# ranback_all.net
KiCad netlist of a schematic drawn in EAGLE
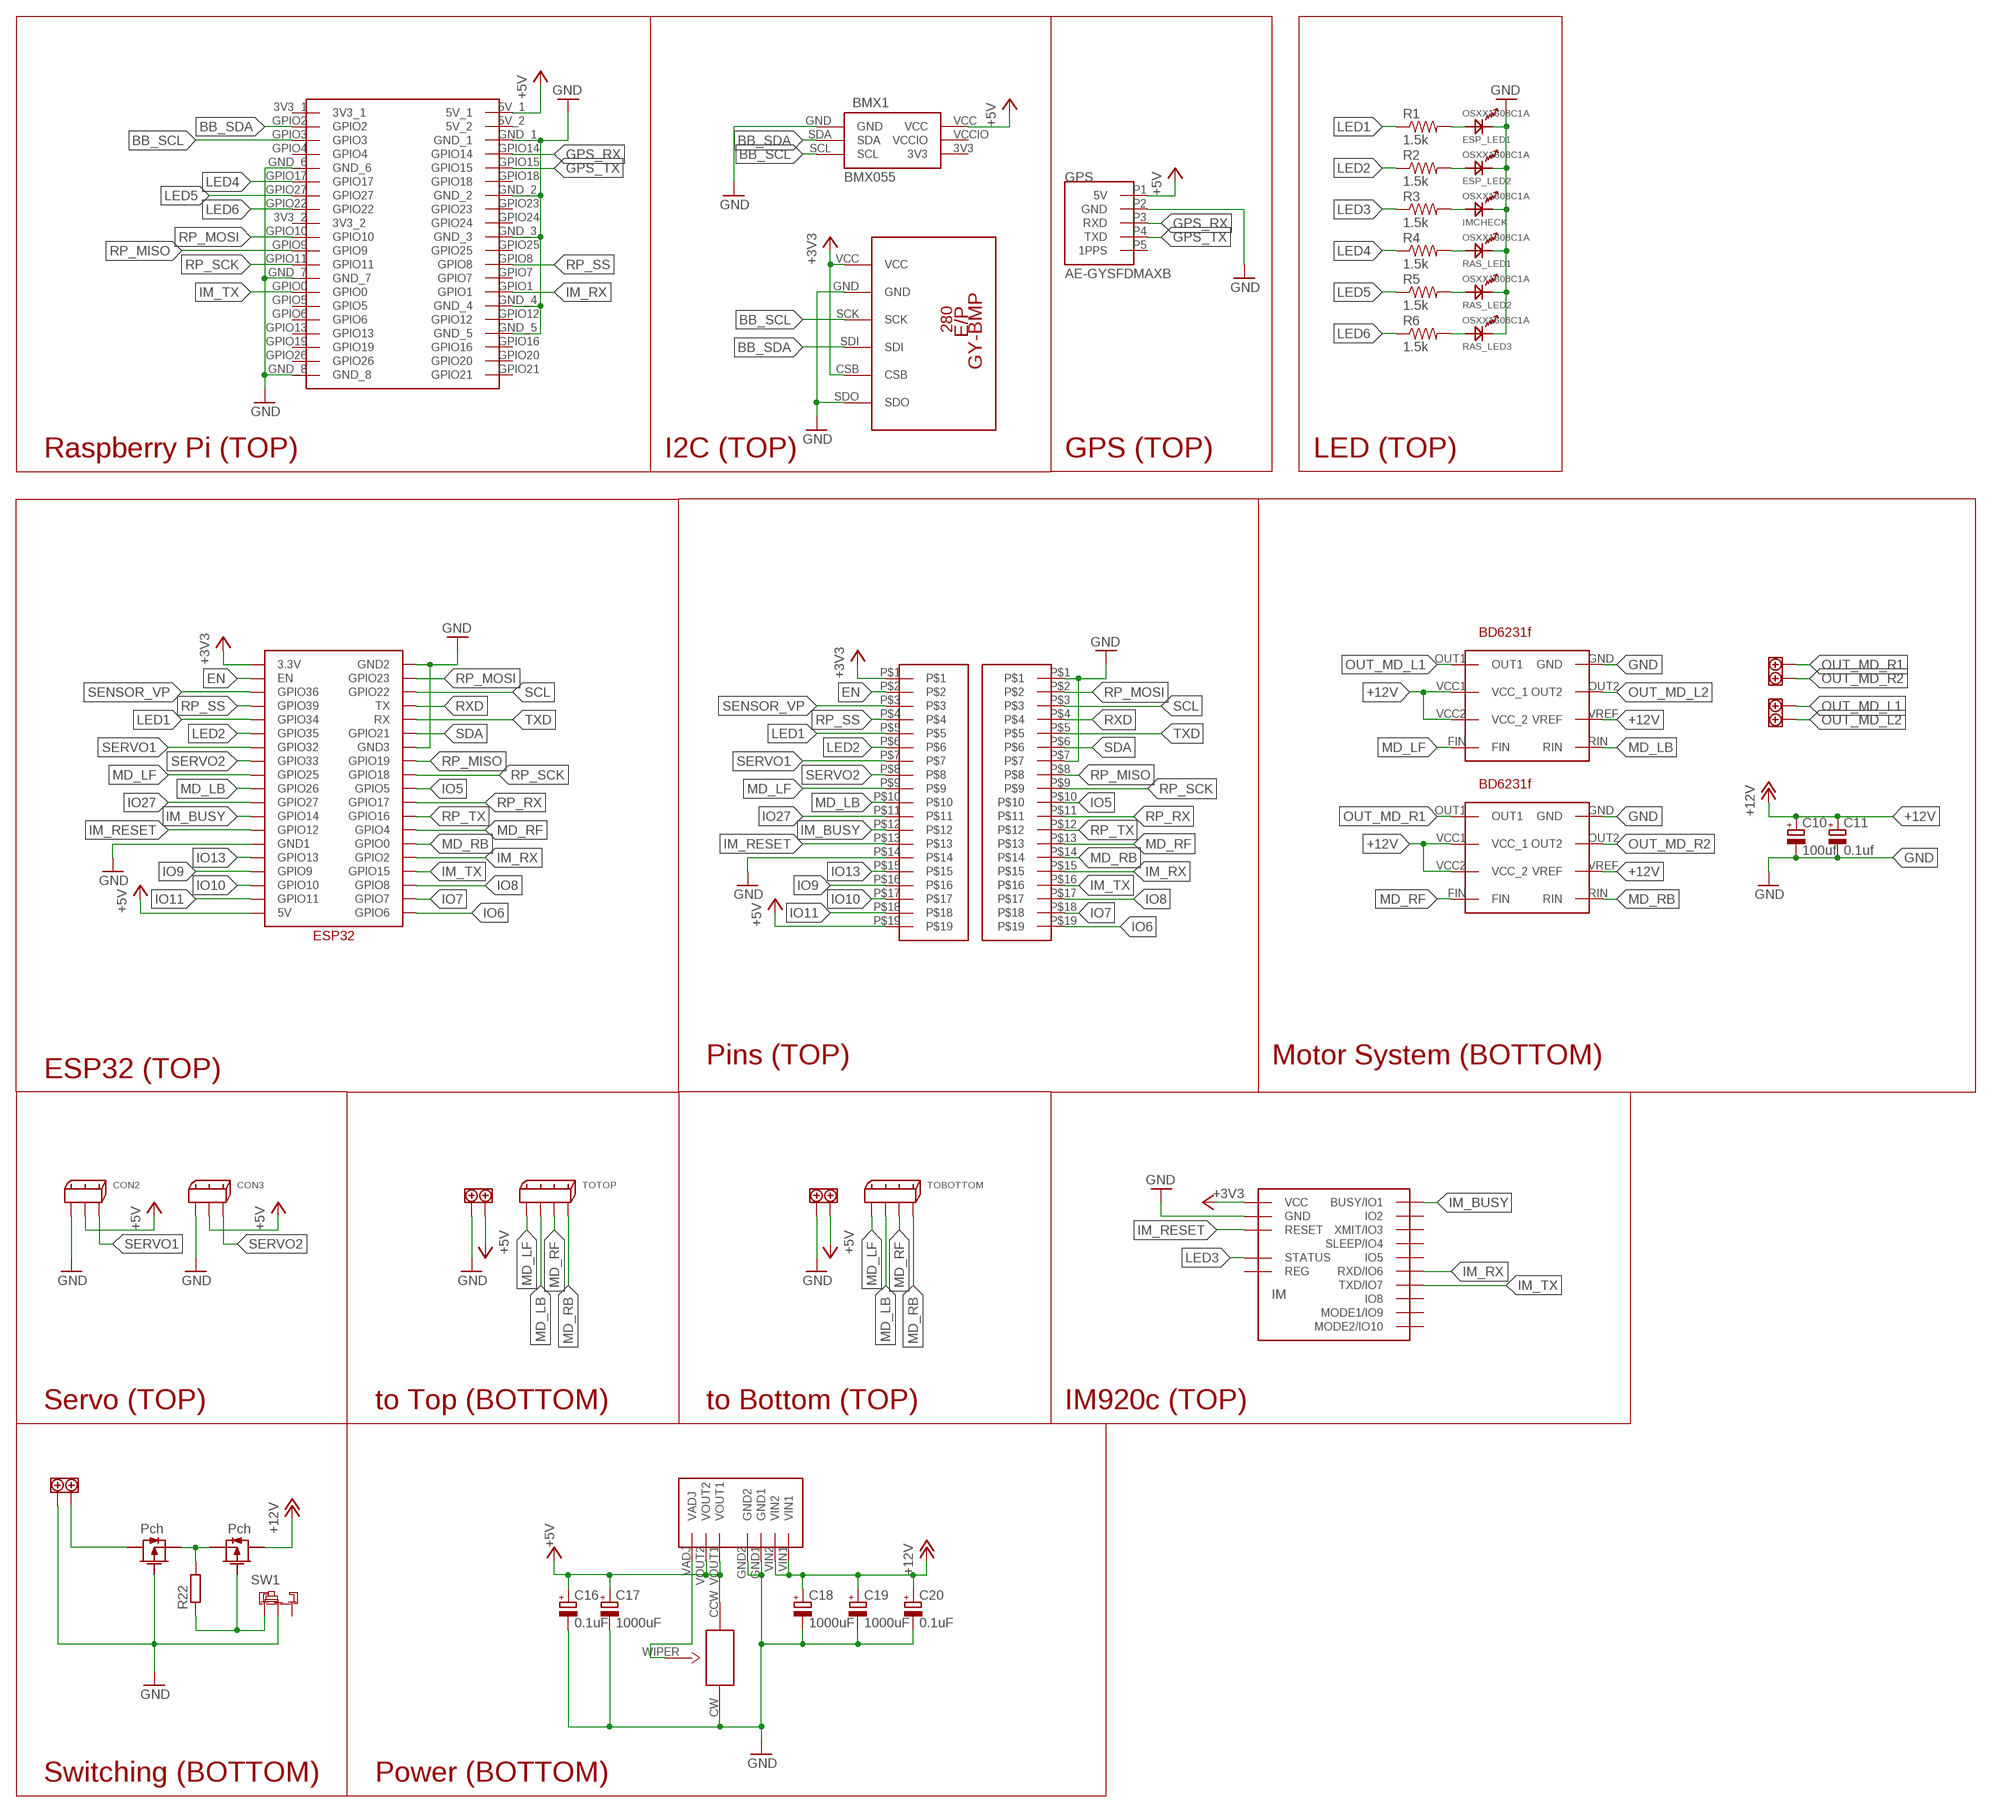
[diagram p0: schematic, sheet 1]

(export (version "E")
  (design (tool "Eeschema 10.0.6"))
  (components
    (comp (ref "100KR1")
      (value "100kR")
      (footprint "eagle-import:3362P")
      (libsource (lib "eagle-import") (part "3362P"))
    )
    (comp (ref "BMX1")
      (value "BMX055")
      (footprint "eagle-import:BMX055")
      (libsource (lib "eagle-import") (part "BMX055"))
    )
    (comp (ref "C10")
      (value "100uf")
      (footprint "eagle-import:E2,5-7")
      (libsource (lib "eagle-import") (part "CPOL-EUE2.5-7"))
    )
    (comp (ref "C11")
      (value "0.1uf")
      (footprint "eagle-import:E2,5-7")
      (libsource (lib "eagle-import") (part "CPOL-EUE2.5-7"))
    )
    (comp (ref "C16")
      (value "0.1uF")
      (footprint "eagle-import:E2,5-7")
      (libsource (lib "eagle-import") (part "CPOL-EUE2.5-7"))
    )
    (comp (ref "C17")
      (value "1000uF")
      (footprint "eagle-import:E5-10,5")
      (libsource (lib "eagle-import") (part "CPOL-EUE5-10.5"))
    )
    (comp (ref "C18")
      (value "1000uF")
      (footprint "eagle-import:E5-10,5")
      (libsource (lib "eagle-import") (part "CPOL-EUE5-10.5"))
    )
    (comp (ref "C19")
      (value "1000uF")
      (footprint "eagle-import:E5-10,5")
      (libsource (lib "eagle-import") (part "CPOL-EUE5-10.5"))
    )
    (comp (ref "C20")
      (value "0.1uF")
      (footprint "eagle-import:E2,5-7")
      (libsource (lib "eagle-import") (part "CPOL-EUE2.5-7"))
    )
    (comp (ref "CON2")
      (value "2.5_MINI-SPOX_3PIN")
      (footprint "eagle-import:2.5_MINI-SPOX_3PIN")
      (libsource (lib "eagle-import") (part "2.5_MINI-SPOX_3PIN"))
    )
    (comp (ref "CON3")
      (value "2.5_MINI-SPOX_3PIN")
      (footprint "eagle-import:2.5_MINI-SPOX_3PIN")
      (libsource (lib "eagle-import") (part "2.5_MINI-SPOX_3PIN"))
    )
    (comp (ref "ESP_LED1")
      (value "OSXX1608C1A")
      (footprint "eagle-import:OSXX1608C1A")
      (libsource (lib "eagle-import") (part "OSXX1608C1A"))
    )
    (comp (ref "ESP_LED2")
      (value "OSXX1608C1A")
      (footprint "eagle-import:OSXX1608C1A")
      (libsource (lib "eagle-import") (part "OSXX1608C1A"))
    )
    (comp (ref "GPS")
      (value "AE-GYSFDMAXB")
      (footprint "eagle-import:AE-GYSFDMAXB")
      (libsource (lib "eagle-import") (part "AE-GYSFDMAXB"))
    )
    (comp (ref "IM")
      (value "IM920C")
      (footprint "eagle-import:IM920C")
      (libsource (lib "eagle-import") (part "IM920C"))
    )
    (comp (ref "IMCHECK")
      (value "OSXX1608C1A")
      (footprint "eagle-import:OSXX1608C1A")
      (libsource (lib "eagle-import") (part "OSXX1608C1A"))
    )
    (comp (ref "MD_L")
      (value "BD6231F")
      (footprint "eagle-import:BD6231F")
      (libsource (lib "eagle-import") (part "BD6231F"))
    )
    (comp (ref "MD_R")
      (value "BD6231F")
      (footprint "eagle-import:BD6231F")
      (libsource (lib "eagle-import") (part "BD6231F"))
    )
    (comp (ref "PIN_L")
      (value "19_2.54")
      (footprint "eagle-import:19_2.54")
      (libsource (lib "eagle-import") (part "19_2.54"))
    )
    (comp (ref "PIN_R")
      (value "19_2.54")
      (footprint "eagle-import:19_2.54")
      (libsource (lib "eagle-import") (part "19_2.54"))
    )
    (comp (ref "R1")
      (value "1.5k")
      (footprint "eagle-import:R0603")
      (libsource (lib "eagle-import") (part "R-US_R0603"))
    )
    (comp (ref "R2")
      (value "1.5k")
      (footprint "eagle-import:R0603")
      (libsource (lib "eagle-import") (part "R-US_R0603"))
    )
    (comp (ref "R3")
      (value "1.5k")
      (footprint "eagle-import:R0603")
      (libsource (lib "eagle-import") (part "R-US_R0603"))
    )
    (comp (ref "R4")
      (value "1.5k")
      (footprint "eagle-import:R0603")
      (libsource (lib "eagle-import") (part "R-US_R0603"))
    )
    (comp (ref "R5")
      (value "1.5k")
      (footprint "eagle-import:R0603")
      (libsource (lib "eagle-import") (part "R-US_R0603"))
    )
    (comp (ref "R6")
      (value "1.5k")
      (footprint "eagle-import:R0603")
      (libsource (lib "eagle-import") (part "R-US_R0603"))
    )
    (comp (ref "R22")
      (value "R-EU_0207/10")
      (footprint "eagle-import:0207_10")
      (libsource (lib "eagle-import") (part "R-EU_0207/10"))
    )
    (comp (ref "RASPBERRYPI_4B")
      (value "RASPBERRYPI4B")
      (footprint "eagle-import:RASPBERRYPI4B")
      (libsource (lib "eagle-import") (part "RASPBERRYPI4B"))
    )
    (comp (ref "RAS_LED1")
      (value "OSXX1608C1A")
      (footprint "eagle-import:OSXX1608C1A")
      (libsource (lib "eagle-import") (part "OSXX1608C1A"))
    )
    (comp (ref "RAS_LED2")
      (value "OSXX1608C1A")
      (footprint "eagle-import:OSXX1608C1A")
      (libsource (lib "eagle-import") (part "OSXX1608C1A"))
    )
    (comp (ref "RAS_LED3")
      (value "OSXX1608C1A")
      (footprint "eagle-import:OSXX1608C1A")
      (libsource (lib "eagle-import") (part "OSXX1608C1A"))
    )
    (comp (ref "SW1")
      (value "SRIDE_SWITCH")
      (footprint "eagle-import:SRIDE_SWITCH")
      (libsource (lib "eagle-import") (part "SRIDE_SWITCH"))
    )
    (comp (ref "TM1")
      (value "TERMINAL_SLOPED_2PIN")
      (footprint "eagle-import:TERMINAL_SLOPED_2PIN")
      (libsource (lib "eagle-import") (part "TERMINAL_SLOPED_2PIN"))
    )
    (comp (ref "TM2")
      (value "TERMINAL_SLOPED_2PIN")
      (footprint "eagle-import:TERMINAL_SLOPED_2PIN")
      (libsource (lib "eagle-import") (part "TERMINAL_SLOPED_2PIN"))
    )
    (comp (ref "TM3")
      (value "TERMINAL_SLOPED_2PIN")
      (footprint "eagle-import:TERMINAL_SLOPED_2PIN")
      (libsource (lib "eagle-import") (part "TERMINAL_SLOPED_2PIN"))
    )
    (comp (ref "TM4")
      (value "TERMINAL_SLOPED_2PIN")
      (footprint "eagle-import:TERMINAL_SLOPED_2PIN")
      (libsource (lib "eagle-import") (part "TERMINAL_SLOPED_2PIN"))
    )
    (comp (ref "TM5")
      (value "TERMINAL_SLOPED_2PIN")
      (footprint "eagle-import:TERMINAL_SLOPED_2PIN")
      (libsource (lib "eagle-import") (part "TERMINAL_SLOPED_2PIN"))
    )
    (comp (ref "TOBOTTOM")
      (value "2.5_MINI-SPOX_4PIN")
      (footprint "eagle-import:2.5_MINI-SPOX_4PIN")
      (libsource (lib "eagle-import") (part "2.5_MINI-SPOX_4PIN"))
    )
    (comp (ref "TOTOP")
      (value "2.5_MINI-SPOX_4PIN")
      (footprint "eagle-import:2.5_MINI-SPOX_4PIN")
      (libsource (lib "eagle-import") (part "2.5_MINI-SPOX_4PIN"))
    )
    (comp (ref "U$2")
      (value "ESP32")
      (footprint "eagle-import:ESP32")
      (libsource (lib "eagle-import") (part "ESP32"))
    )
    (comp (ref "U$7")
      (value "2SJ681-PCH")
      (footprint "eagle-import:2SJ681")
      (libsource (lib "eagle-import") (part "2SJ681-PCH"))
    )
    (comp (ref "U$8")
      (value "5V3A_KIC-053")
      (footprint "eagle-import:5V3A_KIC-053")
      (libsource (lib "eagle-import") (part "5V3A_KIC-053"))
    )
    (comp (ref "U$9")
      (value "GY-BPM280")
      (footprint "eagle-import:GY-BMP280-FOOTPRINT")
      (libsource (lib "eagle-import") (part "GY-BPM280"))
    )
    (comp (ref "U$10")
      (value "2SJ681-PCH")
      (footprint "eagle-import:2SJ681")
      (libsource (lib "eagle-import") (part "2SJ681-PCH"))
    )
  )
  (nets
    (net (code "1") (name "+3V3") (class "Default")
      (node (ref "IM") (pin "$P17") (pinfunction "VCC_$P17") (pintype "bidirectional"))
      (node (ref "PIN_L") (pin "P$1") (pinfunction "P$1_P$1") (pintype "bidirectional"))
      (node (ref "U$2") (pin "3.3V") (pinfunction "3.3V_3.3V") (pintype "bidirectional"))
      (node (ref "U$9") (pin "CSB") (pinfunction "CSB_CSB") (pintype "bidirectional"))
      (node (ref "U$9") (pin "VCC") (pinfunction "VCC_VCC") (pintype "bidirectional"))
    )
    (net (code "2") (name "+5V") (class "Default")
      (node (ref "100KR1") (pin "CCW") (pinfunction "CCW_CCW") (pintype "bidirectional"))
      (node (ref "BMX1") (pin "VCC") (pinfunction "VCC_VCC") (pintype "power_in"))
      (node (ref "C16") (pin "+") (pinfunction "+_+") (pintype "passive"))
      (node (ref "C17") (pin "+") (pinfunction "+_+") (pintype "passive"))
      (node (ref "CON2") (pin "2") (pinfunction "2_2") (pintype "bidirectional"))
      (node (ref "CON3") (pin "2") (pinfunction "2_2") (pintype "bidirectional"))
      (node (ref "GPS") (pin "P1") (pinfunction "5V_P1") (pintype "bidirectional"))
      (node (ref "PIN_L") (pin "P$19") (pinfunction "P$19_P$19") (pintype "bidirectional"))
      (node (ref "RASPBERRYPI_4B") (pin "5V_1") (pinfunction "5V_1_5V_1") (pintype "bidirectional"))
      (node (ref "TM4") (pin "1") (pinfunction "1_1") (pintype "bidirectional"))
      (node (ref "TM5") (pin "1") (pinfunction "1_1") (pintype "bidirectional"))
      (node (ref "U$2") (pin "5V") (pinfunction "5V_5V") (pintype "bidirectional"))
      (node (ref "U$8") (pin "VOUT1") (pinfunction "VOUT1_VOUT1") (pintype "bidirectional"))
      (node (ref "U$8") (pin "VOUT2") (pinfunction "VOUT2_VOUT2") (pintype "bidirectional"))
    )
    (net (code "3") (name "+12V") (class "Default")
      (node (ref "C10") (pin "+") (pinfunction "+_+") (pintype "passive"))
      (node (ref "C11") (pin "+") (pinfunction "+_+") (pintype "passive"))
      (node (ref "C18") (pin "+") (pinfunction "+_+") (pintype "passive"))
      (node (ref "C19") (pin "+") (pinfunction "+_+") (pintype "passive"))
      (node (ref "C20") (pin "+") (pinfunction "+_+") (pintype "passive"))
      (node (ref "MD_L") (pin "VCC1") (pinfunction "VCC_1_VCC1") (pintype "bidirectional"))
      (node (ref "MD_L") (pin "VCC2") (pinfunction "VCC_2_VCC2") (pintype "bidirectional"))
      (node (ref "MD_L") (pin "VREF") (pinfunction "VREF_VREF") (pintype "bidirectional"))
      (node (ref "MD_R") (pin "VCC1") (pinfunction "VCC_1_VCC1") (pintype "bidirectional"))
      (node (ref "MD_R") (pin "VCC2") (pinfunction "VCC_2_VCC2") (pintype "bidirectional"))
      (node (ref "MD_R") (pin "VREF") (pinfunction "VREF_VREF") (pintype "bidirectional"))
      (node (ref "U$10") (pin "DRAIN") (pinfunction "DRAIN_DRAIN") (pintype "bidirectional"))
      (node (ref "U$8") (pin "VIN1") (pinfunction "VIN1_VIN1") (pintype "bidirectional"))
      (node (ref "U$8") (pin "VIN2") (pinfunction "VIN2_VIN2") (pintype "bidirectional"))
    )
    (net (code "4") (name "/3V3") (class "Default")
      (node (ref "BMX1") (pin "3V3") (pinfunction "3V3_3V3") (pintype "power_in"))
    )
    (net (code "5") (name "/VCCIO") (class "Default")
      (node (ref "BMX1") (pin "VCCIO") (pinfunction "VCCIO_VCCIO") (pintype "power_in"))
    )
    (net (code "6") (name "BB_SCL") (class "Default")
      (node (ref "BMX1") (pin "SCL") (pinfunction "SCL_SCL") (pintype "bidirectional"))
      (node (ref "RASPBERRYPI_4B") (pin "GPIO3") (pinfunction "GPIO3_GPIO3") (pintype "bidirectional"))
      (node (ref "U$9") (pin "SCK") (pinfunction "SCK_SCK") (pintype "bidirectional"))
    )
    (net (code "7") (name "BB_SDA") (class "Default")
      (node (ref "BMX1") (pin "SDA") (pinfunction "SDA_SDA") (pintype "bidirectional"))
      (node (ref "RASPBERRYPI_4B") (pin "GPIO2") (pinfunction "GPIO2_GPIO2") (pintype "bidirectional"))
      (node (ref "U$9") (pin "SDI") (pinfunction "SDI_SDI") (pintype "bidirectional"))
    )
    (net (code "8") (name "EN") (class "Default")
      (node (ref "PIN_L") (pin "P$2") (pinfunction "P$2_P$2") (pintype "bidirectional"))
      (node (ref "U$2") (pin "EN") (pinfunction "EN_EN") (pintype "bidirectional"))
    )
    (net (code "9") (name "GND") (class "Default")
      (node (ref "100KR1") (pin "CW") (pinfunction "CW_CW") (pintype "bidirectional"))
      (node (ref "BMX1") (pin "GND") (pinfunction "GND_GND") (pintype "power_in"))
      (node (ref "C10") (pin "-") (pinfunction "-_-") (pintype "passive"))
      (node (ref "C11") (pin "-") (pinfunction "-_-") (pintype "passive"))
      (node (ref "C16") (pin "-") (pinfunction "-_-") (pintype "passive"))
      (node (ref "C17") (pin "-") (pinfunction "-_-") (pintype "passive"))
      (node (ref "C18") (pin "-") (pinfunction "-_-") (pintype "passive"))
      (node (ref "C19") (pin "-") (pinfunction "-_-") (pintype "passive"))
      (node (ref "C20") (pin "-") (pinfunction "-_-") (pintype "passive"))
      (node (ref "CON2") (pin "1") (pinfunction "1_1") (pintype "bidirectional"))
      (node (ref "CON3") (pin "1") (pinfunction "1_1") (pintype "bidirectional"))
      (node (ref "ESP_LED1") (pin "CT") (pinfunction "CT_CT") (pintype "bidirectional"))
      (node (ref "ESP_LED2") (pin "CT") (pinfunction "CT_CT") (pintype "bidirectional"))
      (node (ref "GPS") (pin "P2") (pinfunction "GND_P2") (pintype "bidirectional"))
      (node (ref "IM") (pin "$P18") (pinfunction "GND_$P18") (pintype "bidirectional"))
      (node (ref "IMCHECK") (pin "CT") (pinfunction "CT_CT") (pintype "bidirectional"))
      (node (ref "MD_L") (pin "GND") (pinfunction "GND_GND") (pintype "bidirectional"))
      (node (ref "MD_R") (pin "GND") (pinfunction "GND_GND") (pintype "bidirectional"))
      (node (ref "PIN_L") (pin "P$14") (pinfunction "P$14_P$14") (pintype "bidirectional"))
      (node (ref "PIN_R") (pin "P$1") (pinfunction "P$1_P$1") (pintype "bidirectional"))
      (node (ref "PIN_R") (pin "P$7") (pinfunction "P$7_P$7") (pintype "bidirectional"))
      (node (ref "RASPBERRYPI_4B") (pin "GND_1") (pinfunction "GND_1_GND_1") (pintype "bidirectional"))
      (node (ref "RASPBERRYPI_4B") (pin "GND_2") (pinfunction "GND_2_GND_2") (pintype "bidirectional"))
      (node (ref "RASPBERRYPI_4B") (pin "GND_3") (pinfunction "GND_3_GND_3") (pintype "bidirectional"))
      (node (ref "RASPBERRYPI_4B") (pin "GND_4") (pinfunction "GND_4_GND_4") (pintype "bidirectional"))
      (node (ref "RASPBERRYPI_4B") (pin "GND_5") (pinfunction "GND_5_GND_5") (pintype "bidirectional"))
      (node (ref "RASPBERRYPI_4B") (pin "GND_6") (pinfunction "GND_6_GND_6") (pintype "bidirectional"))
      (node (ref "RASPBERRYPI_4B") (pin "GND_7") (pinfunction "GND_7_GND_7") (pintype "bidirectional"))
      (node (ref "RASPBERRYPI_4B") (pin "GND_8") (pinfunction "GND_8_GND_8") (pintype "bidirectional"))
      (node (ref "RAS_LED1") (pin "CT") (pinfunction "CT_CT") (pintype "bidirectional"))
      (node (ref "RAS_LED2") (pin "CT") (pinfunction "CT_CT") (pintype "bidirectional"))
      (node (ref "RAS_LED3") (pin "CT") (pinfunction "CT_CT") (pintype "bidirectional"))
      (node (ref "SW1") (pin "LR") (pinfunction "LR_LR") (pintype "bidirectional"))
      (node (ref "TM3") (pin "2") (pinfunction "2_2") (pintype "bidirectional"))
      (node (ref "TM4") (pin "2") (pinfunction "2_2") (pintype "bidirectional"))
      (node (ref "TM5") (pin "2") (pinfunction "2_2") (pintype "bidirectional"))
      (node (ref "U$2") (pin "GND1") (pinfunction "GND1_GND1") (pintype "bidirectional"))
      (node (ref "U$2") (pin "GND2") (pinfunction "GND2_GND2") (pintype "bidirectional"))
      (node (ref "U$2") (pin "GND3") (pinfunction "GND3_GND3") (pintype "bidirectional"))
      (node (ref "U$7") (pin "GATE") (pinfunction "GATE_GATE") (pintype "bidirectional"))
      (node (ref "U$8") (pin "GND1") (pinfunction "GND1_GND1") (pintype "bidirectional"))
      (node (ref "U$8") (pin "GND2") (pinfunction "GND2_GND2") (pintype "bidirectional"))
      (node (ref "U$9") (pin "GND") (pinfunction "GND_GND") (pintype "bidirectional"))
      (node (ref "U$9") (pin "SDO") (pinfunction "SDO_SDO") (pintype "bidirectional"))
    )
    (net (code "10") (name "GPS_RX") (class "Default")
      (node (ref "GPS") (pin "P3") (pinfunction "RXD_P3") (pintype "bidirectional"))
      (node (ref "RASPBERRYPI_4B") (pin "GPIO14") (pinfunction "GPIO14_GPIO14") (pintype "bidirectional"))
    )
    (net (code "11") (name "GPS_TX") (class "Default")
      (node (ref "GPS") (pin "P4") (pinfunction "TXD_P4") (pintype "bidirectional"))
      (node (ref "RASPBERRYPI_4B") (pin "GPIO15") (pinfunction "GPIO15_GPIO15") (pintype "bidirectional"))
    )
    (net (code "12") (name "IM_BUSY") (class "Default")
      (node (ref "IM") (pin "$P1") (pinfunction "BUSY/IO1_$P1") (pintype "bidirectional"))
      (node (ref "PIN_L") (pin "P$12") (pinfunction "P$12_P$12") (pintype "bidirectional"))
      (node (ref "U$2") (pin "GPIO14") (pinfunction "GPIO14_GPIO14") (pintype "bidirectional"))
    )
    (net (code "13") (name "IM_RESET") (class "Default")
      (node (ref "IM") (pin "$P19") (pinfunction "RESET_$P19") (pintype "bidirectional"))
      (node (ref "PIN_L") (pin "P$13") (pinfunction "P$13_P$13") (pintype "bidirectional"))
      (node (ref "U$2") (pin "GPIO12") (pinfunction "GPIO12_GPIO12") (pintype "bidirectional"))
    )
    (net (code "14") (name "IM_RX") (class "Default")
      (node (ref "IM") (pin "$P6") (pinfunction "RXD/IO6_$P6") (pintype "bidirectional"))
      (node (ref "PIN_R") (pin "P$15") (pinfunction "P$15_P$15") (pintype "bidirectional"))
      (node (ref "RASPBERRYPI_4B") (pin "GPIO1") (pinfunction "GPIO1_GPIO1") (pintype "bidirectional"))
      (node (ref "U$2") (pin "GPIO2") (pinfunction "GPIO2_GPIO2") (pintype "bidirectional"))
    )
    (net (code "15") (name "IM_TX") (class "Default")
      (node (ref "IM") (pin "$P7") (pinfunction "TXD/IO7_$P7") (pintype "bidirectional"))
      (node (ref "PIN_R") (pin "P$16") (pinfunction "P$16_P$16") (pintype "bidirectional"))
      (node (ref "RASPBERRYPI_4B") (pin "GPIO0") (pinfunction "GPIO0_GPIO0") (pintype "bidirectional"))
      (node (ref "U$2") (pin "GPIO15") (pinfunction "GPIO15_GPIO15") (pintype "bidirectional"))
    )
    (net (code "16") (name "IO5") (class "Default")
      (node (ref "PIN_R") (pin "P$10") (pinfunction "P$10_P$10") (pintype "bidirectional"))
      (node (ref "U$2") (pin "GPIO5") (pinfunction "GPIO5_GPIO5") (pintype "bidirectional"))
    )
    (net (code "17") (name "IO6") (class "Default")
      (node (ref "PIN_R") (pin "P$19") (pinfunction "P$19_P$19") (pintype "bidirectional"))
      (node (ref "U$2") (pin "GPIO6") (pinfunction "GPIO6_GPIO6") (pintype "bidirectional"))
    )
    (net (code "18") (name "IO7") (class "Default")
      (node (ref "PIN_R") (pin "P$18") (pinfunction "P$18_P$18") (pintype "bidirectional"))
      (node (ref "U$2") (pin "GPIO7") (pinfunction "GPIO7_GPIO7") (pintype "bidirectional"))
    )
    (net (code "19") (name "IO8") (class "Default")
      (node (ref "PIN_R") (pin "P$17") (pinfunction "P$17_P$17") (pintype "bidirectional"))
      (node (ref "U$2") (pin "GPIO8") (pinfunction "GPIO8_GPIO8") (pintype "bidirectional"))
    )
    (net (code "20") (name "IO9") (class "Default")
      (node (ref "PIN_L") (pin "P$16") (pinfunction "P$16_P$16") (pintype "bidirectional"))
      (node (ref "U$2") (pin "GPIO9") (pinfunction "GPIO9_GPIO9") (pintype "bidirectional"))
    )
    (net (code "21") (name "IO10") (class "Default")
      (node (ref "PIN_L") (pin "P$17") (pinfunction "P$17_P$17") (pintype "bidirectional"))
      (node (ref "U$2") (pin "GPIO10") (pinfunction "GPIO10_GPIO10") (pintype "bidirectional"))
    )
    (net (code "22") (name "IO11") (class "Default")
      (node (ref "PIN_L") (pin "P$18") (pinfunction "P$18_P$18") (pintype "bidirectional"))
      (node (ref "U$2") (pin "GPIO11") (pinfunction "GPIO11_GPIO11") (pintype "bidirectional"))
    )
    (net (code "23") (name "IO13") (class "Default")
      (node (ref "PIN_L") (pin "P$15") (pinfunction "P$15_P$15") (pintype "bidirectional"))
      (node (ref "U$2") (pin "GPIO13") (pinfunction "GPIO13_GPIO13") (pintype "bidirectional"))
    )
    (net (code "24") (name "IO27") (class "Default")
      (node (ref "PIN_L") (pin "P$11") (pinfunction "P$11_P$11") (pintype "bidirectional"))
      (node (ref "U$2") (pin "GPIO27") (pinfunction "GPIO27_GPIO27") (pintype "bidirectional"))
    )
    (net (code "25") (name "LED1") (class "Default")
      (node (ref "PIN_L") (pin "P$5") (pinfunction "P$5_P$5") (pintype "bidirectional"))
      (node (ref "R1") (pin "1") (pinfunction "1_1") (pintype "passive"))
      (node (ref "U$2") (pin "GPIO34") (pinfunction "GPIO34_GPIO34") (pintype "bidirectional"))
    )
    (net (code "26") (name "LED2") (class "Default")
      (node (ref "PIN_L") (pin "P$6") (pinfunction "P$6_P$6") (pintype "bidirectional"))
      (node (ref "R2") (pin "1") (pinfunction "1_1") (pintype "passive"))
      (node (ref "U$2") (pin "GPIO35") (pinfunction "GPIO35_GPIO35") (pintype "bidirectional"))
    )
    (net (code "27") (name "LED3") (class "Default")
      (node (ref "IM") (pin "$P15") (pinfunction "STATUS_$P15") (pintype "bidirectional"))
      (node (ref "R3") (pin "1") (pinfunction "1_1") (pintype "passive"))
    )
    (net (code "28") (name "LED4") (class "Default")
      (node (ref "R4") (pin "1") (pinfunction "1_1") (pintype "passive"))
      (node (ref "RASPBERRYPI_4B") (pin "GPIO17") (pinfunction "GPIO17_GPIO17") (pintype "bidirectional"))
    )
    (net (code "29") (name "LED5") (class "Default")
      (node (ref "R5") (pin "1") (pinfunction "1_1") (pintype "passive"))
      (node (ref "RASPBERRYPI_4B") (pin "GPIO27") (pinfunction "GPIO27_GPIO27") (pintype "bidirectional"))
    )
    (net (code "30") (name "LED6") (class "Default")
      (node (ref "R6") (pin "1") (pinfunction "1_1") (pintype "passive"))
      (node (ref "RASPBERRYPI_4B") (pin "GPIO22") (pinfunction "GPIO22_GPIO22") (pintype "bidirectional"))
    )
    (net (code "31") (name "MD_LB") (class "Default")
      (node (ref "MD_L") (pin "RIN") (pinfunction "RIN_RIN") (pintype "bidirectional"))
      (node (ref "PIN_L") (pin "P$10") (pinfunction "P$10_P$10") (pintype "bidirectional"))
      (node (ref "TOBOTTOM") (pin "P$2") (pinfunction "2_P$2") (pintype "bidirectional"))
      (node (ref "TOTOP") (pin "P$2") (pinfunction "2_P$2") (pintype "bidirectional"))
      (node (ref "U$2") (pin "GPIO26") (pinfunction "GPIO26_GPIO26") (pintype "bidirectional"))
    )
    (net (code "32") (name "MD_LF") (class "Default")
      (node (ref "MD_L") (pin "FIN") (pinfunction "FIN_FIN") (pintype "bidirectional"))
      (node (ref "PIN_L") (pin "P$9") (pinfunction "P$9_P$9") (pintype "bidirectional"))
      (node (ref "TOBOTTOM") (pin "P$1") (pinfunction "1_P$1") (pintype "bidirectional"))
      (node (ref "TOTOP") (pin "P$1") (pinfunction "1_P$1") (pintype "bidirectional"))
      (node (ref "U$2") (pin "GPIO25") (pinfunction "GPIO25_GPIO25") (pintype "bidirectional"))
    )
    (net (code "33") (name "MD_RB") (class "Default")
      (node (ref "MD_R") (pin "RIN") (pinfunction "RIN_RIN") (pintype "bidirectional"))
      (node (ref "PIN_R") (pin "P$14") (pinfunction "P$14_P$14") (pintype "bidirectional"))
      (node (ref "TOBOTTOM") (pin "P$4") (pinfunction "4_P$4") (pintype "bidirectional"))
      (node (ref "TOTOP") (pin "P$4") (pinfunction "4_P$4") (pintype "bidirectional"))
      (node (ref "U$2") (pin "GPIO0") (pinfunction "GPIO0_GPIO0") (pintype "bidirectional"))
    )
    (net (code "34") (name "MD_RF") (class "Default")
      (node (ref "MD_R") (pin "FIN") (pinfunction "FIN_FIN") (pintype "bidirectional"))
      (node (ref "PIN_R") (pin "P$13") (pinfunction "P$13_P$13") (pintype "bidirectional"))
      (node (ref "TOBOTTOM") (pin "P$3") (pinfunction "3_P$3") (pintype "bidirectional"))
      (node (ref "TOTOP") (pin "P$3") (pinfunction "3_P$3") (pintype "bidirectional"))
      (node (ref "U$2") (pin "GPIO4") (pinfunction "GPIO4_GPIO4") (pintype "bidirectional"))
    )
    (net (code "35") (name "Net-(100KR1-PadWIPER)") (class "Default")
      (node (ref "100KR1") (pin "WIPER") (pinfunction "WIPER_WIPER") (pintype "bidirectional"))
      (node (ref "U$8") (pin "VADJ") (pinfunction "VADJ_VADJ") (pintype "bidirectional"))
    )
    (net (code "36") (name "Net-(ESP_LED1-PadAN)") (class "Default")
      (node (ref "ESP_LED1") (pin "AN") (pinfunction "AN_AN") (pintype "bidirectional"))
      (node (ref "R1") (pin "2") (pinfunction "2_2") (pintype "passive"))
    )
    (net (code "37") (name "Net-(ESP_LED2-PadAN)") (class "Default")
      (node (ref "ESP_LED2") (pin "AN") (pinfunction "AN_AN") (pintype "bidirectional"))
      (node (ref "R2") (pin "2") (pinfunction "2_2") (pintype "passive"))
    )
    (net (code "38") (name "Net-(IMCHECK-PadAN)") (class "Default")
      (node (ref "IMCHECK") (pin "AN") (pinfunction "AN_AN") (pintype "bidirectional"))
      (node (ref "R3") (pin "2") (pinfunction "2_2") (pintype "passive"))
    )
    (net (code "39") (name "Net-(R4-Pad2)") (class "Default")
      (node (ref "R4") (pin "2") (pinfunction "2_2") (pintype "passive"))
      (node (ref "RAS_LED1") (pin "AN") (pinfunction "AN_AN") (pintype "bidirectional"))
    )
    (net (code "40") (name "Net-(R5-Pad2)") (class "Default")
      (node (ref "R5") (pin "2") (pinfunction "2_2") (pintype "passive"))
      (node (ref "RAS_LED2") (pin "AN") (pinfunction "AN_AN") (pintype "bidirectional"))
    )
    (net (code "41") (name "Net-(R6-Pad2)") (class "Default")
      (node (ref "R6") (pin "2") (pinfunction "2_2") (pintype "passive"))
      (node (ref "RAS_LED3") (pin "AN") (pinfunction "AN_AN") (pintype "bidirectional"))
    )
    (net (code "42") (name "Net-(R22-Pad1)") (class "Default")
      (node (ref "R22") (pin "1") (pinfunction "1_1") (pintype "passive"))
      (node (ref "SW1") (pin "L") (pinfunction "L_L") (pintype "bidirectional"))
      (node (ref "U$10") (pin "GATE") (pinfunction "GATE_GATE") (pintype "bidirectional"))
    )
    (net (code "43") (name "Net-(R22-Pad2)") (class "Default")
      (node (ref "R22") (pin "2") (pinfunction "2_2") (pintype "passive"))
      (node (ref "U$10") (pin "SOURCE") (pinfunction "SOURCE_SOURCE") (pintype "bidirectional"))
      (node (ref "U$7") (pin "SOURCE") (pinfunction "SOURCE_SOURCE") (pintype "bidirectional"))
    )
    (net (code "44") (name "Net-(TM3-Pad1)") (class "Default")
      (node (ref "TM3") (pin "1") (pinfunction "1_1") (pintype "bidirectional"))
      (node (ref "U$7") (pin "DRAIN") (pinfunction "DRAIN_DRAIN") (pintype "bidirectional"))
    )
    (net (code "45") (name "OUT_MD_L1") (class "Default")
      (node (ref "MD_L") (pin "OUT1") (pinfunction "OUT1_OUT1") (pintype "bidirectional"))
      (node (ref "TM2") (pin "1") (pinfunction "1_1") (pintype "bidirectional"))
    )
    (net (code "46") (name "OUT_MD_L2") (class "Default")
      (node (ref "MD_L") (pin "OUT2") (pinfunction "OUT2_OUT2") (pintype "bidirectional"))
      (node (ref "TM2") (pin "2") (pinfunction "2_2") (pintype "bidirectional"))
    )
    (net (code "47") (name "OUT_MD_R1") (class "Default")
      (node (ref "MD_R") (pin "OUT1") (pinfunction "OUT1_OUT1") (pintype "bidirectional"))
      (node (ref "TM1") (pin "1") (pinfunction "1_1") (pintype "bidirectional"))
    )
    (net (code "48") (name "OUT_MD_R2") (class "Default")
      (node (ref "MD_R") (pin "OUT2") (pinfunction "OUT2_OUT2") (pintype "bidirectional"))
      (node (ref "TM1") (pin "2") (pinfunction "2_2") (pintype "bidirectional"))
    )
    (net (code "49") (name "RP_MISO") (class "Default")
      (node (ref "PIN_R") (pin "P$8") (pinfunction "P$8_P$8") (pintype "bidirectional"))
      (node (ref "RASPBERRYPI_4B") (pin "GPIO9") (pinfunction "GPIO9_GPIO9") (pintype "bidirectional"))
      (node (ref "U$2") (pin "GPIO19") (pinfunction "GPIO19_GPIO19") (pintype "bidirectional"))
    )
    (net (code "50") (name "RP_MOSI") (class "Default")
      (node (ref "PIN_R") (pin "P$2") (pinfunction "P$2_P$2") (pintype "bidirectional"))
      (node (ref "RASPBERRYPI_4B") (pin "GPIO10") (pinfunction "GPIO10_GPIO10") (pintype "bidirectional"))
      (node (ref "U$2") (pin "GPIO23") (pinfunction "GPIO23_GPIO23") (pintype "bidirectional"))
    )
    (net (code "51") (name "RP_RX") (class "Default")
      (node (ref "PIN_R") (pin "P$11") (pinfunction "P$11_P$11") (pintype "bidirectional"))
      (node (ref "U$2") (pin "GPIO17") (pinfunction "GPIO17_GPIO17") (pintype "bidirectional"))
    )
    (net (code "52") (name "RP_SCK") (class "Default")
      (node (ref "PIN_R") (pin "P$9") (pinfunction "P$9_P$9") (pintype "bidirectional"))
      (node (ref "RASPBERRYPI_4B") (pin "GPIO11") (pinfunction "GPIO11_GPIO11") (pintype "bidirectional"))
      (node (ref "U$2") (pin "GPIO18") (pinfunction "GPIO18_GPIO18") (pintype "bidirectional"))
    )
    (net (code "53") (name "RP_SS") (class "Default")
      (node (ref "PIN_L") (pin "P$4") (pinfunction "P$4_P$4") (pintype "bidirectional"))
      (node (ref "RASPBERRYPI_4B") (pin "GPIO8") (pinfunction "GPIO8_GPIO8") (pintype "bidirectional"))
      (node (ref "U$2") (pin "GPIO39") (pinfunction "GPIO39_GPIO39") (pintype "bidirectional"))
    )
    (net (code "54") (name "RP_TX") (class "Default")
      (node (ref "PIN_R") (pin "P$12") (pinfunction "P$12_P$12") (pintype "bidirectional"))
      (node (ref "U$2") (pin "GPIO16") (pinfunction "GPIO16_GPIO16") (pintype "bidirectional"))
    )
    (net (code "55") (name "RXD") (class "Default")
      (node (ref "PIN_R") (pin "P$4") (pinfunction "P$4_P$4") (pintype "bidirectional"))
      (node (ref "U$2") (pin "TX") (pinfunction "TX_TX") (pintype "bidirectional"))
    )
    (net (code "56") (name "SCL") (class "Default")
      (node (ref "PIN_R") (pin "P$3") (pinfunction "P$3_P$3") (pintype "bidirectional"))
      (node (ref "U$2") (pin "GPIO22") (pinfunction "GPIO22_GPIO22") (pintype "bidirectional"))
    )
    (net (code "57") (name "SDA") (class "Default")
      (node (ref "PIN_R") (pin "P$6") (pinfunction "P$6_P$6") (pintype "bidirectional"))
      (node (ref "U$2") (pin "GPIO21") (pinfunction "GPIO21_GPIO21") (pintype "bidirectional"))
    )
    (net (code "58") (name "SENSOR_VP") (class "Default")
      (node (ref "PIN_L") (pin "P$3") (pinfunction "P$3_P$3") (pintype "bidirectional"))
      (node (ref "U$2") (pin "GPIO36") (pinfunction "GPIO36_GPIO36") (pintype "bidirectional"))
    )
    (net (code "59") (name "SERVO1") (class "Default")
      (node (ref "CON2") (pin "3") (pinfunction "3_3") (pintype "bidirectional"))
      (node (ref "PIN_L") (pin "P$7") (pinfunction "P$7_P$7") (pintype "bidirectional"))
      (node (ref "U$2") (pin "GPIO32") (pinfunction "GPIO32_GPIO32") (pintype "bidirectional"))
    )
    (net (code "60") (name "SERVO2") (class "Default")
      (node (ref "CON3") (pin "3") (pinfunction "3_3") (pintype "bidirectional"))
      (node (ref "PIN_L") (pin "P$8") (pinfunction "P$8_P$8") (pintype "bidirectional"))
      (node (ref "U$2") (pin "GPIO33") (pinfunction "GPIO33_GPIO33") (pintype "bidirectional"))
    )
    (net (code "61") (name "TXD") (class "Default")
      (node (ref "PIN_R") (pin "P$5") (pinfunction "P$5_P$5") (pintype "bidirectional"))
      (node (ref "U$2") (pin "RX") (pinfunction "RX_RX") (pintype "bidirectional"))
    )
    (net (code "62") (name "unconnected-(GPS-1PPS-PadP5)") (class "Default")
      (node (ref "GPS") (pin "P5") (pinfunction "1PPS_P5") (pintype "bidirectional"))
    )
    (net (code "63") (name "unconnected-(IM-IO2-Pad$P2)") (class "Default")
      (node (ref "IM") (pin "$P2") (pinfunction "IO2_$P2") (pintype "bidirectional"))
    )
    (net (code "64") (name "unconnected-(IM-IO5-Pad$P5)") (class "Default")
      (node (ref "IM") (pin "$P5") (pinfunction "IO5_$P5") (pintype "bidirectional"))
    )
    (net (code "65") (name "unconnected-(IM-IO8-Pad$P8)") (class "Default")
      (node (ref "IM") (pin "$P8") (pinfunction "IO8_$P8") (pintype "bidirectional"))
    )
    (net (code "66") (name "unconnected-(IM-MODE1{slash}IO9-Pad$P9)") (class "Default")
      (node (ref "IM") (pin "$P9") (pinfunction "MODE1/IO9_$P9") (pintype "bidirectional"))
    )
    (net (code "67") (name "unconnected-(IM-MODE2{slash}IO10-Pad$P10)") (class "Default")
      (node (ref "IM") (pin "$P10") (pinfunction "MODE2/IO10_$P10") (pintype "bidirectional"))
    )
    (net (code "68") (name "unconnected-(IM-REG-Pad$P16)") (class "Default")
      (node (ref "IM") (pin "$P16") (pinfunction "REG_$P16") (pintype "bidirectional"))
    )
    (net (code "69") (name "unconnected-(IM-SLEEP{slash}IO4-Pad$P4)") (class "Default")
      (node (ref "IM") (pin "$P4") (pinfunction "SLEEP/IO4_$P4") (pintype "bidirectional"))
    )
    (net (code "70") (name "unconnected-(IM-XMIT{slash}IO3-Pad$P3)") (class "Default")
      (node (ref "IM") (pin "$P3") (pinfunction "XMIT/IO3_$P3") (pintype "bidirectional"))
    )
    (net (code "71") (name "unconnected-(RASPBERRYPI_4B-Pad3V3_1)") (class "Default")
      (node (ref "RASPBERRYPI_4B") (pin "3V3_1") (pinfunction "3V3_1_3V3_1") (pintype "bidirectional"))
    )
    (net (code "72") (name "unconnected-(RASPBERRYPI_4B-Pad3V3_2)") (class "Default")
      (node (ref "RASPBERRYPI_4B") (pin "3V3_2") (pinfunction "3V3_2_3V3_2") (pintype "bidirectional"))
    )
    (net (code "73") (name "unconnected-(RASPBERRYPI_4B-Pad5V_2)") (class "Default")
      (node (ref "RASPBERRYPI_4B") (pin "5V_2") (pinfunction "5V_2_5V_2") (pintype "bidirectional"))
    )
    (net (code "74") (name "unconnected-(RASPBERRYPI_4B-PadGPIO4)") (class "Default")
      (node (ref "RASPBERRYPI_4B") (pin "GPIO4") (pinfunction "GPIO4_GPIO4") (pintype "bidirectional"))
    )
    (net (code "75") (name "unconnected-(RASPBERRYPI_4B-PadGPIO5)") (class "Default")
      (node (ref "RASPBERRYPI_4B") (pin "GPIO5") (pinfunction "GPIO5_GPIO5") (pintype "bidirectional"))
    )
    (net (code "76") (name "unconnected-(RASPBERRYPI_4B-PadGPIO6)") (class "Default")
      (node (ref "RASPBERRYPI_4B") (pin "GPIO6") (pinfunction "GPIO6_GPIO6") (pintype "bidirectional"))
    )
    (net (code "77") (name "unconnected-(RASPBERRYPI_4B-PadGPIO7)") (class "Default")
      (node (ref "RASPBERRYPI_4B") (pin "GPIO7") (pinfunction "GPIO7_GPIO7") (pintype "bidirectional"))
    )
    (net (code "78") (name "unconnected-(RASPBERRYPI_4B-PadGPIO12)") (class "Default")
      (node (ref "RASPBERRYPI_4B") (pin "GPIO12") (pinfunction "GPIO12_GPIO12") (pintype "bidirectional"))
    )
    (net (code "79") (name "unconnected-(RASPBERRYPI_4B-PadGPIO13)") (class "Default")
      (node (ref "RASPBERRYPI_4B") (pin "GPIO13") (pinfunction "GPIO13_GPIO13") (pintype "bidirectional"))
    )
    (net (code "80") (name "unconnected-(RASPBERRYPI_4B-PadGPIO16)") (class "Default")
      (node (ref "RASPBERRYPI_4B") (pin "GPIO16") (pinfunction "GPIO16_GPIO16") (pintype "bidirectional"))
    )
    (net (code "81") (name "unconnected-(RASPBERRYPI_4B-PadGPIO18)") (class "Default")
      (node (ref "RASPBERRYPI_4B") (pin "GPIO18") (pinfunction "GPIO18_GPIO18") (pintype "bidirectional"))
    )
    (net (code "82") (name "unconnected-(RASPBERRYPI_4B-PadGPIO19)") (class "Default")
      (node (ref "RASPBERRYPI_4B") (pin "GPIO19") (pinfunction "GPIO19_GPIO19") (pintype "bidirectional"))
    )
    (net (code "83") (name "unconnected-(RASPBERRYPI_4B-PadGPIO20)") (class "Default")
      (node (ref "RASPBERRYPI_4B") (pin "GPIO20") (pinfunction "GPIO20_GPIO20") (pintype "bidirectional"))
    )
    (net (code "84") (name "unconnected-(RASPBERRYPI_4B-PadGPIO21)") (class "Default")
      (node (ref "RASPBERRYPI_4B") (pin "GPIO21") (pinfunction "GPIO21_GPIO21") (pintype "bidirectional"))
    )
    (net (code "85") (name "unconnected-(RASPBERRYPI_4B-PadGPIO23)") (class "Default")
      (node (ref "RASPBERRYPI_4B") (pin "GPIO23") (pinfunction "GPIO23_GPIO23") (pintype "bidirectional"))
    )
    (net (code "86") (name "unconnected-(RASPBERRYPI_4B-PadGPIO24)") (class "Default")
      (node (ref "RASPBERRYPI_4B") (pin "GPIO24") (pinfunction "GPIO24_GPIO24") (pintype "bidirectional"))
    )
    (net (code "87") (name "unconnected-(RASPBERRYPI_4B-PadGPIO25)") (class "Default")
      (node (ref "RASPBERRYPI_4B") (pin "GPIO25") (pinfunction "GPIO25_GPIO25") (pintype "bidirectional"))
    )
    (net (code "88") (name "unconnected-(RASPBERRYPI_4B-PadGPIO26)") (class "Default")
      (node (ref "RASPBERRYPI_4B") (pin "GPIO26") (pinfunction "GPIO26_GPIO26") (pintype "bidirectional"))
    )
    (net (code "89") (name "unconnected-(SW1-PadR)") (class "Default")
      (node (ref "SW1") (pin "R") (pinfunction "R_R") (pintype "bidirectional"))
    )
  )
)
